# Clamp-header.net
KiCad netlist of a schematic drawn in EAGLE
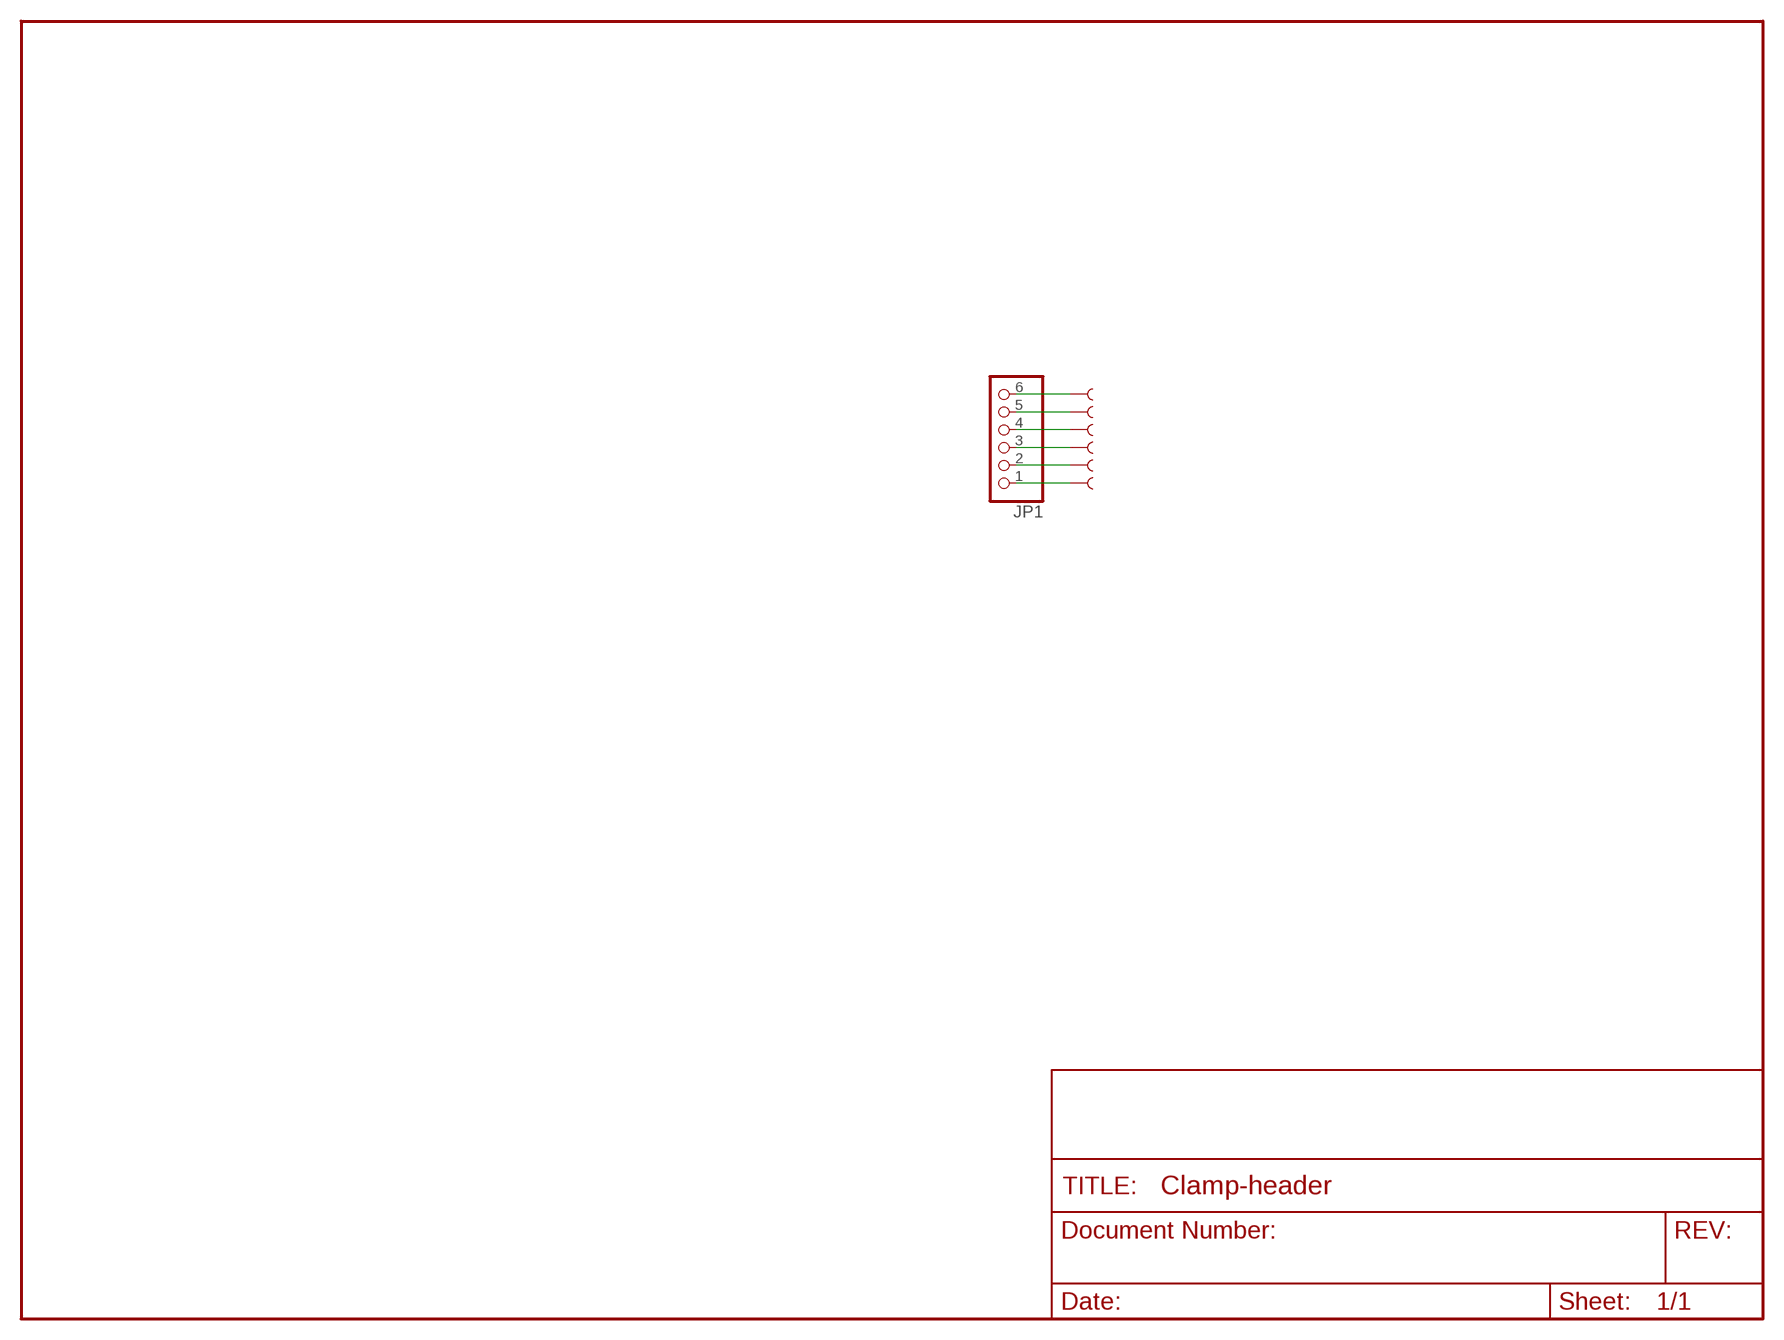
[diagram p0: schematic, sheet 1]

(export (version "E")
  (design (tool "Eeschema 10.0.6"))
  (components
    (comp (ref "JP1")
      (value "PINHD-1X6/90")
      (footprint "eagle-import:1X06_90")
      (libsource (lib "eagle-import") (part "PINHD-1X6/90"))
    )
    (comp (ref "U$1")
      (value "SEWTAP1")
      (footprint "eagle-import:SEWTAP")
      (libsource (lib "eagle-import") (part "SEWTAP1"))
    )
    (comp (ref "U$2")
      (value "SEWTAP1")
      (footprint "eagle-import:SEWTAP")
      (libsource (lib "eagle-import") (part "SEWTAP1"))
    )
    (comp (ref "U$3")
      (value "SEWTAP1")
      (footprint "eagle-import:SEWTAP")
      (libsource (lib "eagle-import") (part "SEWTAP1"))
    )
    (comp (ref "U$5")
      (value "SEWTAP1")
      (footprint "eagle-import:SEWTAP")
      (libsource (lib "eagle-import") (part "SEWTAP1"))
    )
    (comp (ref "U$6")
      (value "SEWTAP1")
      (footprint "eagle-import:SEWTAP")
      (libsource (lib "eagle-import") (part "SEWTAP1"))
    )
    (comp (ref "U$7")
      (value "SEWTAP1")
      (footprint "eagle-import:SEWTAP")
      (libsource (lib "eagle-import") (part "SEWTAP1"))
    )
  )
  (nets
    (net (code "1") (name "Net-(JP1-Pad1)") (class "Default")
      (node (ref "JP1") (pin "1") (pinfunction "1_1") (pintype "passive"))
      (node (ref "U$2") (pin "1") (pinfunction "1_1") (pintype "bidirectional"))
    )
    (net (code "2") (name "Net-(JP1-Pad2)") (class "Default")
      (node (ref "JP1") (pin "2") (pinfunction "2_2") (pintype "passive"))
      (node (ref "U$5") (pin "1") (pinfunction "1_1") (pintype "bidirectional"))
    )
    (net (code "3") (name "Net-(JP1-Pad3)") (class "Default")
      (node (ref "JP1") (pin "3") (pinfunction "3_3") (pintype "passive"))
      (node (ref "U$1") (pin "1") (pinfunction "1_1") (pintype "bidirectional"))
    )
    (net (code "4") (name "Net-(JP1-Pad4)") (class "Default")
      (node (ref "JP1") (pin "4") (pinfunction "4_4") (pintype "passive"))
      (node (ref "U$7") (pin "1") (pinfunction "1_1") (pintype "bidirectional"))
    )
    (net (code "5") (name "Net-(JP1-Pad5)") (class "Default")
      (node (ref "JP1") (pin "5") (pinfunction "5_5") (pintype "passive"))
      (node (ref "U$6") (pin "1") (pinfunction "1_1") (pintype "bidirectional"))
    )
    (net (code "6") (name "Net-(JP1-Pad6)") (class "Default")
      (node (ref "JP1") (pin "6") (pinfunction "6_6") (pintype "passive"))
      (node (ref "U$3") (pin "1") (pinfunction "1_1") (pintype "bidirectional"))
    )
  )
)
